# lpf_30_20.net
KiCad netlist of a schematic drawn in Altium Designer
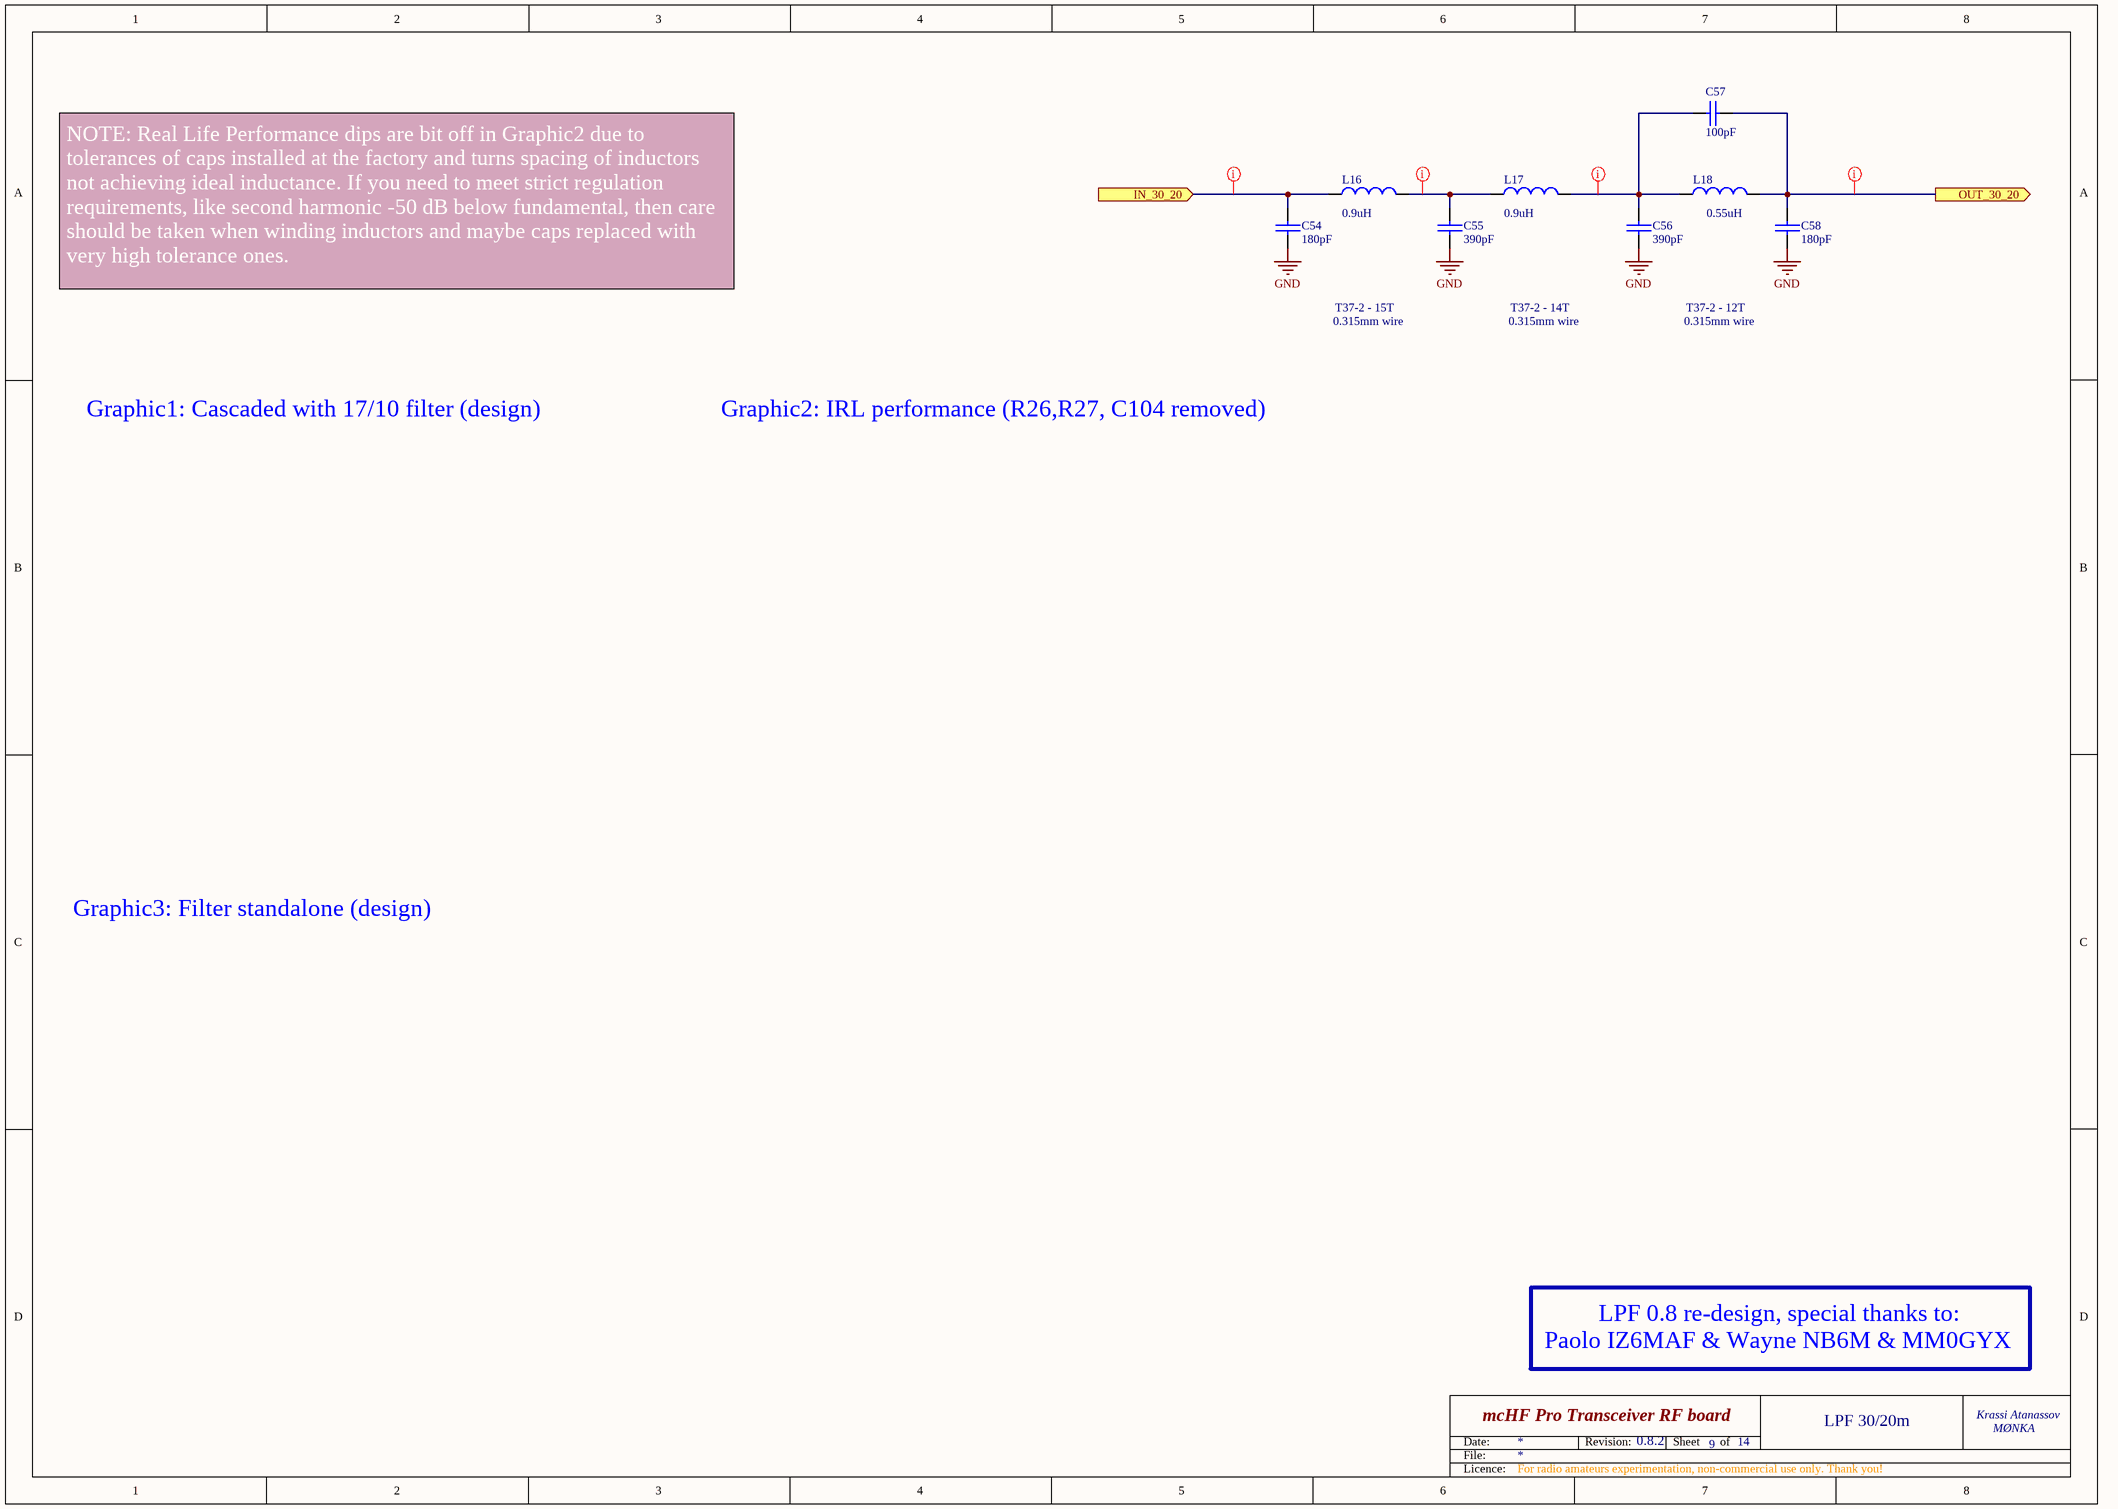
[diagram p0: lpf_30_20.SchDoc]

(export (version "E")
  (design (tool "Eeschema 10.0.6"))
  (components
    (comp (ref "C54")
      (value "180pF")
      (footprint "0805")
      (description "Capacitor")
      (fields (field (name "VOLTAGE") "100V"))
      (libsource (lib "mcHF_rf") (part "CAP"))
    )
    (comp (ref "C55")
      (value "390pF")
      (footprint "0805")
      (description "Capacitor")
      (fields (field (name "VOLTAGE") "100V"))
      (libsource (lib "mcHF_rf") (part "CAP"))
    )
    (comp (ref "C56")
      (value "390pF")
      (footprint "0805")
      (description "Capacitor")
      (fields (field (name "VOLTAGE") "100V"))
      (libsource (lib "mcHF_rf") (part "CAP"))
    )
    (comp (ref "C57")
      (value "100pF")
      (footprint "0805")
      (description "Capacitor")
      (fields (field (name "VOLTAGE") "100V"))
      (libsource (lib "mcHF_rf") (part "CAP"))
    )
    (comp (ref "C58")
      (value "180pF")
      (footprint "0805")
      (description "Capacitor")
      (fields (field (name "VOLTAGE") "100V"))
      (libsource (lib "mcHF_rf") (part "CAP"))
    )
    (comp (ref "L16")
      (value "T37-2")
      (footprint "LPF_IND")
      (description "T37-2 handwound inductor")
      (fields (field (name "INDUCTANCE") "0.9uH"))
      (libsource (lib "mcHF_rf") (part "LPF_IND"))
    )
    (comp (ref "L17")
      (value "T37-2")
      (footprint "LPF_IND")
      (description "T37-2 handwound inductor")
      (fields (field (name "INDUCTANCE") "0.9uH"))
      (libsource (lib "mcHF_rf") (part "LPF_IND"))
    )
    (comp (ref "L18")
      (value "T37-2")
      (footprint "LPF_IND")
      (description "T37-2 handwound inductor")
      (fields (field (name "INDUCTANCE") "0.55uH"))
      (libsource (lib "mcHF_rf") (part "LPF_IND"))
    )
  )
  (nets
    (net (code "1") (name "/IN_30_20") (class "Default")
      (node (ref "C54") (pin "2") (pinfunction "2_2") (pintype "passive"))
      (node (ref "L16") (pin "1") (pinfunction "1_1") (pintype "passive"))
    )
    (net (code "2") (name "/OUT_30_20") (class "Default")
      (node (ref "C57") (pin "1") (pinfunction "1_1") (pintype "passive"))
      (node (ref "C58") (pin "2") (pinfunction "2_2") (pintype "passive"))
      (node (ref "L18") (pin "2") (pinfunction "2_2") (pintype "passive"))
    )
    (net (code "3") (name "GND") (class "Default")
      (node (ref "C54") (pin "1") (pinfunction "1_1") (pintype "passive"))
      (node (ref "C55") (pin "1") (pinfunction "1_1") (pintype "passive"))
      (node (ref "C56") (pin "1") (pinfunction "1_1") (pintype "passive"))
      (node (ref "C58") (pin "1") (pinfunction "1_1") (pintype "passive"))
    )
    (net (code "4") (name "Net-(C55-Pad2)") (class "Default")
      (node (ref "C55") (pin "2") (pinfunction "2_2") (pintype "passive"))
      (node (ref "L16") (pin "2") (pinfunction "2_2") (pintype "passive"))
      (node (ref "L17") (pin "1") (pinfunction "1_1") (pintype "passive"))
    )
    (net (code "5") (name "Net-(C56-Pad2)") (class "Default")
      (node (ref "C56") (pin "2") (pinfunction "2_2") (pintype "passive"))
      (node (ref "C57") (pin "2") (pinfunction "2_2") (pintype "passive"))
      (node (ref "L17") (pin "2") (pinfunction "2_2") (pintype "passive"))
      (node (ref "L18") (pin "1") (pinfunction "1_1") (pintype "passive"))
    )
  )
)
